# MBus-WeMOS.net
KiCad netlist of a schematic drawn in EAGLE
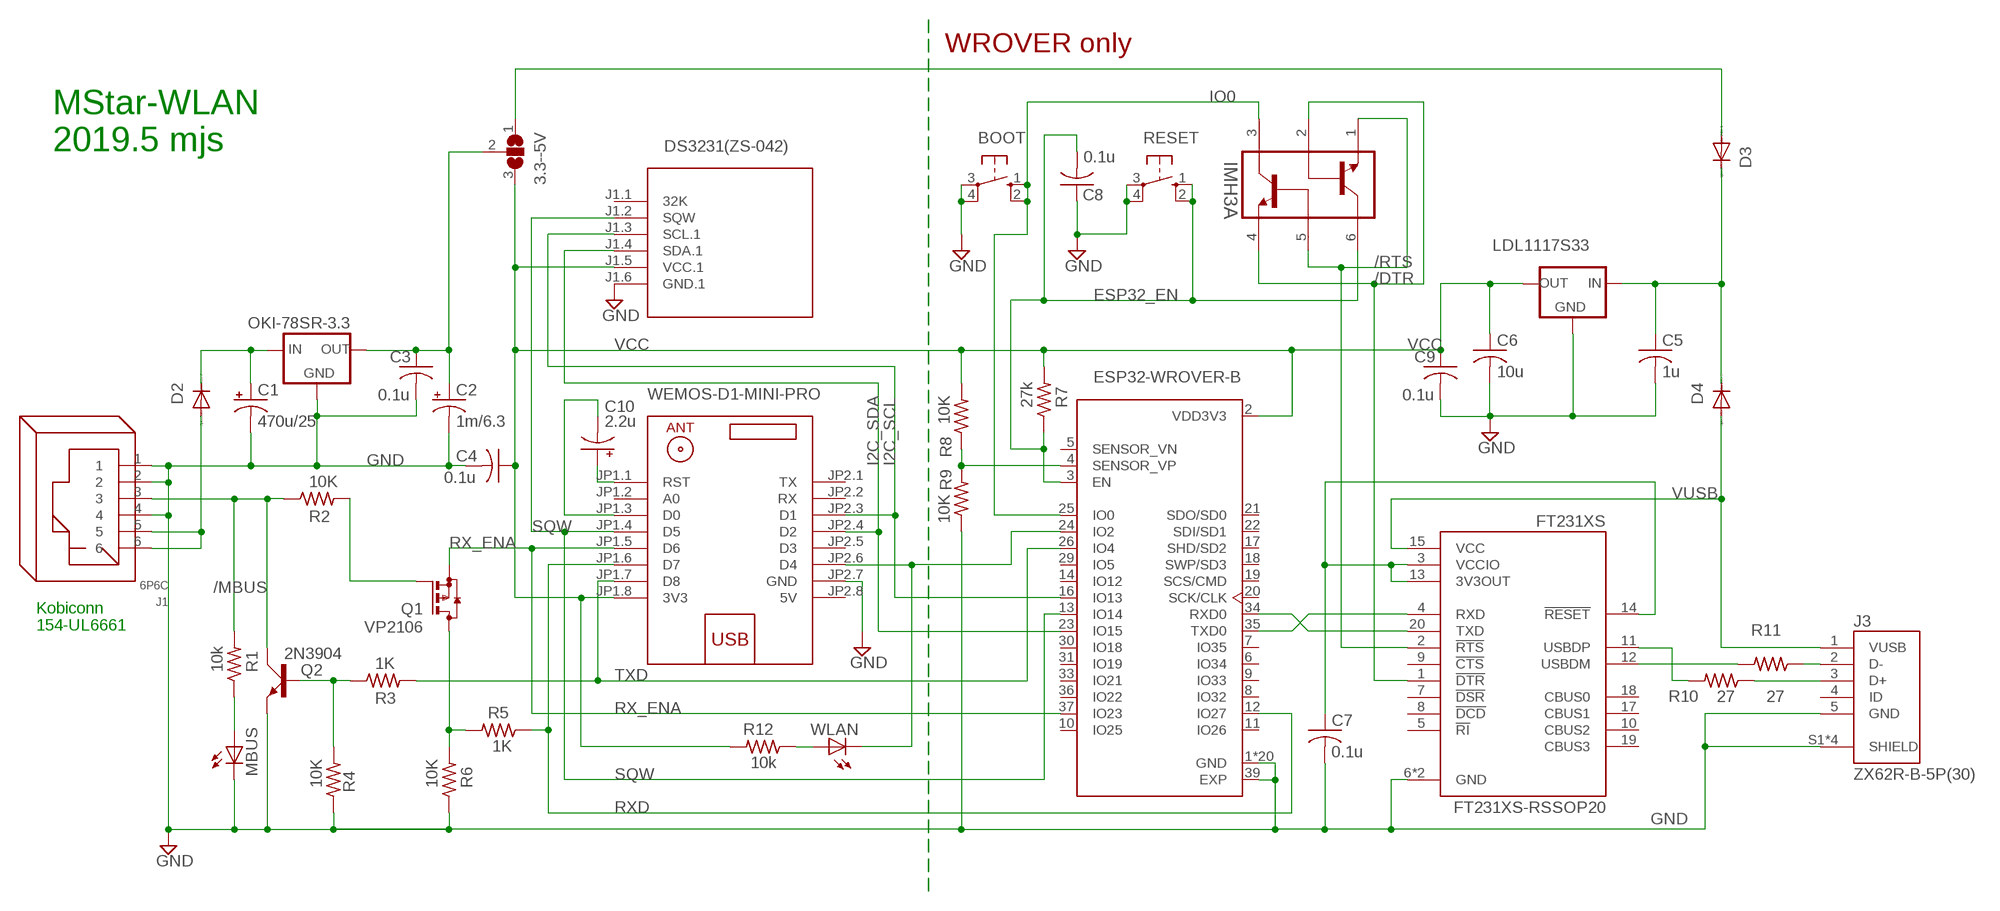
[diagram p0: schematic, sheet 1]

(export (version "E")
  (design (tool "Eeschema 10.0.6"))
  (components
    (comp (ref "3.3--5V")
      (value "SJ2W")
      (footprint "eagle-import:SJ_2")
      (libsource (lib "eagle-import") (part "SJ2W"))
    )
    (comp (ref "BOOT")
      (value "10-XX")
      (footprint "eagle-import:B3F-10XX")
      (fields (field (name "MPN") "B3F-1000"))
      (libsource (lib "eagle-import") (part "10-XX"))
    )
    (comp (ref "C1")
      (value "470u/25")
      (footprint "eagle-import:E3,5-8")
      (libsource (lib "eagle-import") (part "CPOL-USE3.5-8"))
    )
    (comp (ref "C2")
      (value "1m/6.3")
      (footprint "eagle-import:E5-10,5")
      (libsource (lib "eagle-import") (part "CPOL-USE5-10.5"))
    )
    (comp (ref "C3")
      (value "0.1u")
      (footprint "eagle-import:C025-024X044")
      (libsource (lib "eagle-import") (part "C-US025-024X044"))
    )
    (comp (ref "C4")
      (value "0.1u")
      (footprint "eagle-import:C025-024X044")
      (libsource (lib "eagle-import") (part "C-US025-024X044"))
    )
    (comp (ref "C5")
      (value "1u")
      (footprint "eagle-import:C1206")
      (libsource (lib "eagle-import") (part "C-USC1206"))
    )
    (comp (ref "C6")
      (value "10u")
      (footprint "eagle-import:C1206")
      (libsource (lib "eagle-import") (part "C-USC1206"))
    )
    (comp (ref "C7")
      (value "0.1u")
      (footprint "eagle-import:C025-024X044")
      (libsource (lib "eagle-import") (part "C-US025-024X044"))
    )
    (comp (ref "C8")
      (value "0.1u")
      (footprint "eagle-import:C025-024X044")
      (libsource (lib "eagle-import") (part "C-US025-024X044"))
    )
    (comp (ref "C9")
      (value "0.1u")
      (footprint "eagle-import:C025-024X044")
      (libsource (lib "eagle-import") (part "C-US025-024X044"))
    )
    (comp (ref "C10")
      (value "2.2u")
      (footprint "eagle-import:E2,5-5")
      (libsource (lib "eagle-import") (part "CPOL-USE2.5-5"))
    )
    (comp (ref "D2")
      (value "DIODE-D-5")
      (footprint "eagle-import:D-5")
      (libsource (lib "eagle-import") (part "DIODE-D-5"))
    )
    (comp (ref "D3")
      (value "DIODE-D-5")
      (footprint "eagle-import:D-5")
      (libsource (lib "eagle-import") (part "DIODE-D-5"))
    )
    (comp (ref "D4")
      (value "DIODE-D-5")
      (footprint "eagle-import:D-5")
      (libsource (lib "eagle-import") (part "DIODE-D-5"))
    )
    (comp (ref "DS3231(ZS-042)")
      (value "RTC-DS3231-AT24C32-6")
      (footprint "eagle-import:RTC-DS3231-AT24C32-6")
      (libsource (lib "eagle-import") (part "RTC-DS3231-AT24C32-6"))
    )
    (comp (ref "ESP32-WROVER-B")
      (value "ESP32-WROVER-I")
      (footprint "eagle-import:XCVR_ESP32-WROVER-I")
      (fields (field (name "MF") "Espressif Systems"))
      (libsource (lib "eagle-import") (part "ESP32-WROVER-I"))
    )
    (comp (ref "FT231XS")
      (value "FT231XS-RSSOP20")
      (footprint "eagle-import:SSOP20")
      (fields
        (field (name "DIGI-KEY_PART_NUMBER") "768-1129-1-ND")
        (field (name "MF") "FTDI,")
        (field (name "MP") "FT231XS-R")
      )
      (libsource (lib "eagle-import") (part "FT231XS-RSSOP20"))
    )
    (comp (ref "IMH3A")
      (value "IMH3ATSOP6")
      (footprint "eagle-import:TSOP6")
      (libsource (lib "eagle-import") (part "IMH3ATSOP6"))
    )
    (comp (ref "J1")
      (value "6P6C")
      (footprint "eagle-import:RJ12")
      (libsource (lib "eagle-import") (part "RJ12"))
    )
    (comp (ref "J3")
      (value "ZX62R-B-5P(30)")
      (footprint "eagle-import:HRS_ZX62R-B-5P(30)")
      (fields (field (name "MF") "Hirose") (field (name "MP") "ZX62R-B-5P_30_"))
      (libsource (lib "eagle-import") (part "ZX62R-B-5P(30)"))
    )
    (comp (ref "LDL1117S33")
      (value "LM1117MP-3.3")
      (footprint "eagle-import:SOT223")
      (fields (field (name "MF") "Texas Instruments"))
      (libsource (lib "eagle-import") (part "LM1117?-MP3.3"))
    )
    (comp (ref "MBUS")
      (value "LED3MM")
      (footprint "eagle-import:LED3MM")
      (libsource (lib "eagle-import") (part "LED3MM"))
    )
    (comp (ref "OKI-78SR-3.3")
      (value "78MXXS")
      (footprint "eagle-import:78MXXS")
      (libsource (lib "eagle-import") (part "78MXXS"))
    )
    (comp (ref "Q1")
      (value "VP2106")
      (footprint "eagle-import:TO92")
      (libsource (lib "eagle-import") (part "VP2106"))
    )
    (comp (ref "Q2")
      (value "2N3904")
      (footprint "eagle-import:TO92D")
      (libsource (lib "eagle-import") (part "2N3904"))
    )
    (comp (ref "R1")
      (value "10k")
      (footprint "eagle-import:0207_2V")
      (libsource (lib "eagle-import") (part "R-US_0207/2V"))
    )
    (comp (ref "R2")
      (value "10K")
      (footprint "eagle-import:0207_2V")
      (libsource (lib "eagle-import") (part "R-US_0207/2V"))
    )
    (comp (ref "R3")
      (value "1K")
      (footprint "eagle-import:0207_2V")
      (libsource (lib "eagle-import") (part "R-US_0207/2V"))
    )
    (comp (ref "R4")
      (value "10K")
      (footprint "eagle-import:0207_2V")
      (libsource (lib "eagle-import") (part "R-US_0207/2V"))
    )
    (comp (ref "R5")
      (value "1K")
      (footprint "eagle-import:0207_2V")
      (libsource (lib "eagle-import") (part "R-US_0207/2V"))
    )
    (comp (ref "R6")
      (value "10K")
      (footprint "eagle-import:0207_2V")
      (libsource (lib "eagle-import") (part "R-US_0207/2V"))
    )
    (comp (ref "R7")
      (value "27k")
      (footprint "eagle-import:0207_2V")
      (libsource (lib "eagle-import") (part "R-US_0207/2V"))
    )
    (comp (ref "R8")
      (value "10K")
      (footprint "eagle-import:0207_2V")
      (libsource (lib "eagle-import") (part "R-US_0207/2V"))
    )
    (comp (ref "R9")
      (value "10K")
      (footprint "eagle-import:0207_2V")
      (libsource (lib "eagle-import") (part "R-US_0207/2V"))
    )
    (comp (ref "R10")
      (value "27")
      (footprint "eagle-import:0207_2V")
      (libsource (lib "eagle-import") (part "R-US_0207/2V"))
    )
    (comp (ref "R11")
      (value "27")
      (footprint "eagle-import:0207_2V")
      (libsource (lib "eagle-import") (part "R-US_0207/2V"))
    )
    (comp (ref "R12")
      (value "10k")
      (footprint "eagle-import:0207_2V")
      (libsource (lib "eagle-import") (part "R-US_0207/2V"))
    )
    (comp (ref "RESET")
      (value "10-XX")
      (footprint "eagle-import:B3F-10XX")
      (fields (field (name "MPN") "B3F-1000"))
      (libsource (lib "eagle-import") (part "10-XX"))
    )
    (comp (ref "U$1")
      (value "WEMOS-D1-MINI-PRO")
      (footprint "eagle-import:WEMOS-D1-MINI-PRO")
      (libsource (lib "eagle-import") (part "WEMOS-D1-MINI-PRO"))
    )
    (comp (ref "WLAN")
      (value "LED3MM")
      (footprint "eagle-import:LED3MM")
      (libsource (lib "eagle-import") (part "LED3MM"))
    )
  )
  (nets
    (net (code "1") (name "/5V") (class "Default")
      (node (ref "U$1") (pin "JP2.8") (pinfunction "5V_JP2.8") (pintype "power_in"))
    )
    (net (code "2") (name "/ESP32_EN") (class "Default")
      (node (ref "C8") (pin "2") (pinfunction "2_2") (pintype "passive"))
      (node (ref "ESP32-WROVER-B") (pin "3") (pinfunction "EN_3") (pintype "input"))
      (node (ref "IMH3A") (pin "6") (pinfunction "Q1C_6") (pintype "bidirectional"))
      (node (ref "R7") (pin "1") (pinfunction "1_1") (pintype "passive"))
      (node (ref "RESET") (pin "1") (pinfunction "S_1") (pintype "passive"))
      (node (ref "RESET") (pin "2") (pinfunction "S1_2") (pintype "passive"))
    )
    (net (code "3") (name "/I2C_SCL") (class "Default")
      (node (ref "DS3231(ZS-042)") (pin "J1.3") (pinfunction "SCL.1_J1.3") (pintype "bidirectional"))
      (node (ref "ESP32-WROVER-B") (pin "16") (pinfunction "IO13_16") (pintype "bidirectional"))
      (node (ref "U$1") (pin "JP2.3") (pinfunction "D1_JP2.3") (pintype "bidirectional"))
    )
    (net (code "4") (name "/I2C_SDA") (class "Default")
      (node (ref "DS3231(ZS-042)") (pin "J1.4") (pinfunction "SDA.1_J1.4") (pintype "bidirectional"))
      (node (ref "ESP32-WROVER-B") (pin "23") (pinfunction "IO15_23") (pintype "bidirectional"))
      (node (ref "U$1") (pin "JP2.4") (pinfunction "D2_JP2.4") (pintype "bidirectional"))
    )
    (net (code "5") (name "/IO0") (class "Default")
      (node (ref "BOOT") (pin "1") (pinfunction "S_1") (pintype "passive"))
      (node (ref "BOOT") (pin "2") (pinfunction "S1_2") (pintype "passive"))
      (node (ref "ESP32-WROVER-B") (pin "25") (pinfunction "IO0_25") (pintype "bidirectional"))
      (node (ref "IMH3A") (pin "3") (pinfunction "Q2C_3") (pintype "bidirectional"))
    )
    (net (code "6") (name "/RXD") (class "Default")
      (node (ref "ESP32-WROVER-B") (pin "12") (pinfunction "IO27_12") (pintype "bidirectional"))
      (node (ref "R5") (pin "1") (pinfunction "1_1") (pintype "passive"))
      (node (ref "U$1") (pin "JP1.6") (pinfunction "D7_JP1.6") (pintype "bidirectional"))
    )
    (net (code "7") (name "/RX_ENA") (class "Default")
      (node (ref "ESP32-WROVER-B") (pin "37") (pinfunction "IO23_37") (pintype "bidirectional"))
      (node (ref "Q1") (pin "S") (pinfunction "S_S") (pintype "passive"))
      (node (ref "U$1") (pin "JP1.5") (pinfunction "D6_JP1.5") (pintype "bidirectional"))
    )
    (net (code "8") (name "/SQW") (class "Default")
      (node (ref "DS3231(ZS-042)") (pin "J1.2") (pinfunction "SQW_J1.2") (pintype "bidirectional"))
      (node (ref "ESP32-WROVER-B") (pin "13") (pinfunction "IO14_13") (pintype "bidirectional"))
      (node (ref "U$1") (pin "JP1.4") (pinfunction "D5_JP1.4") (pintype "bidirectional"))
    )
    (net (code "9") (name "/TXD") (class "Default")
      (node (ref "ESP32-WROVER-B") (pin "26") (pinfunction "IO4_26") (pintype "bidirectional"))
      (node (ref "R3") (pin "2") (pinfunction "2_2") (pintype "passive"))
      (node (ref "U$1") (pin "JP1.7") (pinfunction "D8_JP1.7") (pintype "bidirectional"))
    )
    (net (code "10") (name "/VCC") (class "Default")
      (node (ref "3.3--5V") (pin "3") (pinfunction "3_3") (pintype "passive"))
      (node (ref "C4") (pin "1") (pinfunction "1_1") (pintype "passive"))
      (node (ref "C6") (pin "1") (pinfunction "1_1") (pintype "passive"))
      (node (ref "C9") (pin "1") (pinfunction "1_1") (pintype "passive"))
      (node (ref "DS3231(ZS-042)") (pin "J1.5") (pinfunction "VCC.1_J1.5") (pintype "power_in"))
      (node (ref "ESP32-WROVER-B") (pin "2") (pinfunction "VDD3V3_2") (pintype "power_in"))
      (node (ref "LDL1117S33") (pin "2") (pinfunction "OUT_2") (pintype "passive"))
      (node (ref "LDL1117S33") (pin "4") (pinfunction "OUT_4") (pintype "passive"))
      (node (ref "R12") (pin "2") (pinfunction "2_2") (pintype "passive"))
      (node (ref "R7") (pin "2") (pinfunction "2_2") (pintype "passive"))
      (node (ref "R8") (pin "2") (pinfunction "2_2") (pintype "passive"))
      (node (ref "U$1") (pin "JP1.8") (pinfunction "3V3_JP1.8") (pintype "power_in"))
    )
    (net (code "11") (name "/VUSB") (class "Default")
      (node (ref "D4") (pin "A") (pinfunction "A_A") (pintype "passive"))
      (node (ref "FT231XS") (pin "15") (pinfunction "VCC_15") (pintype "power_in"))
      (node (ref "J3") (pin "1") (pinfunction "VUSB_1") (pintype "passive"))
    )
    (net (code "12") (name "/{slash}DTR") (class "Default")
      (node (ref "FT231XS") (pin "1") (pinfunction "~{DTR}_1") (pintype "output"))
      (node (ref "IMH3A") (pin "2") (pinfunction "Q1B_2") (pintype "bidirectional"))
      (node (ref "IMH3A") (pin "4") (pinfunction "Q2E_4") (pintype "bidirectional"))
    )
    (net (code "13") (name "/{slash}MBUS") (class "Default")
      (node (ref "J1") (pin "3") (pinfunction "3_3") (pintype "bidirectional"))
      (node (ref "Q2") (pin "C") (pinfunction "C_C") (pintype "passive"))
      (node (ref "R1") (pin "2") (pinfunction "2_2") (pintype "passive"))
      (node (ref "R2") (pin "1") (pinfunction "1_1") (pintype "passive"))
    )
    (net (code "14") (name "/{slash}RTS") (class "Default")
      (node (ref "FT231XS") (pin "2") (pinfunction "~{RTS}_2") (pintype "output"))
      (node (ref "IMH3A") (pin "1") (pinfunction "Q1E_1") (pintype "bidirectional"))
      (node (ref "IMH3A") (pin "5") (pinfunction "Q2B_5") (pintype "bidirectional"))
    )
    (net (code "15") (name "GND") (class "Default")
      (node (ref "BOOT") (pin "3") (pinfunction "P_3") (pintype "passive"))
      (node (ref "BOOT") (pin "4") (pinfunction "P1_4") (pintype "passive"))
      (node (ref "C1") (pin "-") (pinfunction "-_-") (pintype "passive"))
      (node (ref "C2") (pin "-") (pinfunction "-_-") (pintype "passive"))
      (node (ref "C3") (pin "2") (pinfunction "2_2") (pintype "passive"))
      (node (ref "C4") (pin "2") (pinfunction "2_2") (pintype "passive"))
      (node (ref "C5") (pin "2") (pinfunction "2_2") (pintype "passive"))
      (node (ref "C6") (pin "2") (pinfunction "2_2") (pintype "passive"))
      (node (ref "C7") (pin "2") (pinfunction "2_2") (pintype "passive"))
      (node (ref "C8") (pin "1") (pinfunction "1_1") (pintype "passive"))
      (node (ref "C9") (pin "2") (pinfunction "2_2") (pintype "passive"))
      (node (ref "DS3231(ZS-042)") (pin "J1.6") (pinfunction "GND.1_J1.6") (pintype "power_in"))
      (node (ref "ESP32-WROVER-B") (pin "1") (pinfunction "GND_1") (pintype "power_in"))
      (node (ref "ESP32-WROVER-B") (pin "15") (pinfunction "GND_15") (pintype "power_in"))
      (node (ref "ESP32-WROVER-B") (pin "38") (pinfunction "GND_38") (pintype "power_in"))
      (node (ref "ESP32-WROVER-B") (pin "39") (pinfunction "EXP_39") (pintype "power_in"))
      (node (ref "ESP32-WROVER-B") (pin "40") (pinfunction "GND_40") (pintype "power_in"))
      (node (ref "ESP32-WROVER-B") (pin "P$1") (pinfunction "GND_P$1") (pintype "power_in"))
      (node (ref "ESP32-WROVER-B") (pin "P$10") (pinfunction "GND_P$10") (pintype "power_in"))
      (node (ref "ESP32-WROVER-B") (pin "P$11") (pinfunction "GND_P$11") (pintype "power_in"))
      (node (ref "ESP32-WROVER-B") (pin "P$12") (pinfunction "GND_P$12") (pintype "power_in"))
      (node (ref "ESP32-WROVER-B") (pin "P$13") (pinfunction "GND_P$13") (pintype "power_in"))
      (node (ref "ESP32-WROVER-B") (pin "P$14") (pinfunction "GND_P$14") (pintype "power_in"))
      (node (ref "ESP32-WROVER-B") (pin "P$15") (pinfunction "GND_P$15") (pintype "power_in"))
      (node (ref "ESP32-WROVER-B") (pin "P$16") (pinfunction "GND_P$16") (pintype "power_in"))
      (node (ref "ESP32-WROVER-B") (pin "P$2") (pinfunction "GND_P$2") (pintype "power_in"))
      (node (ref "ESP32-WROVER-B") (pin "P$3") (pinfunction "GND_P$3") (pintype "power_in"))
      (node (ref "ESP32-WROVER-B") (pin "P$4") (pinfunction "GND_P$4") (pintype "power_in"))
      (node (ref "ESP32-WROVER-B") (pin "P$5") (pinfunction "GND_P$5") (pintype "power_in"))
      (node (ref "ESP32-WROVER-B") (pin "P$6") (pinfunction "GND_P$6") (pintype "power_in"))
      (node (ref "ESP32-WROVER-B") (pin "P$7") (pinfunction "GND_P$7") (pintype "power_in"))
      (node (ref "ESP32-WROVER-B") (pin "P$8") (pinfunction "GND_P$8") (pintype "power_in"))
      (node (ref "ESP32-WROVER-B") (pin "P$9") (pinfunction "GND_P$9") (pintype "power_in"))
      (node (ref "FT231XS") (pin "16") (pinfunction "GND_16") (pintype "power_in"))
      (node (ref "FT231XS") (pin "6") (pinfunction "GND_6") (pintype "power_in"))
      (node (ref "J1") (pin "1") (pinfunction "1_1") (pintype "bidirectional"))
      (node (ref "J1") (pin "2") (pinfunction "2_2") (pintype "bidirectional"))
      (node (ref "J1") (pin "4") (pinfunction "4_4") (pintype "bidirectional"))
      (node (ref "J3") (pin "5") (pinfunction "GND_5") (pintype "passive"))
      (node (ref "J3") (pin "S1") (pinfunction "SHIELD_S1") (pintype "passive"))
      (node (ref "J3") (pin "S2") (pinfunction "SHIELD_S2") (pintype "passive"))
      (node (ref "J3") (pin "S3") (pinfunction "SHIELD_S3") (pintype "passive"))
      (node (ref "J3") (pin "S6") (pinfunction "SHIELD_S6") (pintype "passive"))
      (node (ref "LDL1117S33") (pin "1") (pinfunction "GND_1") (pintype "input"))
      (node (ref "MBUS") (pin "K") (pinfunction "C_K") (pintype "passive"))
      (node (ref "OKI-78SR-3.3") (pin "GND") (pinfunction "GND_GND") (pintype "input"))
      (node (ref "Q2") (pin "E") (pinfunction "E_E") (pintype "passive"))
      (node (ref "R4") (pin "1") (pinfunction "1_1") (pintype "passive"))
      (node (ref "R6") (pin "1") (pinfunction "1_1") (pintype "passive"))
      (node (ref "R9") (pin "1") (pinfunction "1_1") (pintype "passive"))
      (node (ref "RESET") (pin "3") (pinfunction "P_3") (pintype "passive"))
      (node (ref "RESET") (pin "4") (pinfunction "P1_4") (pintype "passive"))
      (node (ref "U$1") (pin "JP2.7") (pinfunction "GND_JP2.7") (pintype "power_in"))
    )
    (net (code "16") (name "Net-(3.3--5V-Pad1)") (class "Default")
      (node (ref "3.3--5V") (pin "1") (pinfunction "1_1") (pintype "passive"))
      (node (ref "D3") (pin "A") (pinfunction "A_A") (pintype "passive"))
    )
    (net (code "17") (name "Net-(3.3--5V-Pad2)") (class "Default")
      (node (ref "3.3--5V") (pin "2") (pinfunction "2_2") (pintype "passive"))
      (node (ref "C2") (pin "+") (pinfunction "+_+") (pintype "passive"))
      (node (ref "C3") (pin "1") (pinfunction "1_1") (pintype "passive"))
      (node (ref "OKI-78SR-3.3") (pin "OUT") (pinfunction "OUT_OUT") (pintype "passive"))
    )
    (net (code "18") (name "Net-(C1-Pad+)") (class "Default")
      (node (ref "C1") (pin "+") (pinfunction "+_+") (pintype "passive"))
      (node (ref "D2") (pin "C") (pinfunction "C_C") (pintype "passive"))
      (node (ref "OKI-78SR-3.3") (pin "IN") (pinfunction "IN_IN") (pintype "input"))
    )
    (net (code "19") (name "Net-(D2-PadA)") (class "Default")
      (node (ref "D2") (pin "A") (pinfunction "A_A") (pintype "passive"))
      (node (ref "J1") (pin "5") (pinfunction "5_5") (pintype "bidirectional"))
      (node (ref "J1") (pin "6") (pinfunction "6_6") (pintype "bidirectional"))
    )
    (net (code "20") (name "Net-(ESP32-WROVER-B-IO2)") (class "Default")
      (node (ref "ESP32-WROVER-B") (pin "24") (pinfunction "IO2_24") (pintype "bidirectional"))
      (node (ref "U$1") (pin "JP2.6") (pinfunction "D4_JP2.6") (pintype "bidirectional"))
      (node (ref "WLAN") (pin "K") (pinfunction "C_K") (pintype "passive"))
    )
    (net (code "21") (name "Net-(ESP32-WROVER-B-RXD0)") (class "Default")
      (node (ref "ESP32-WROVER-B") (pin "34") (pinfunction "RXD0_34") (pintype "bidirectional"))
      (node (ref "FT231XS") (pin "20") (pinfunction "TXD_20") (pintype "output"))
    )
    (net (code "22") (name "Net-(ESP32-WROVER-B-SENSOR_VP)") (class "Default")
      (node (ref "ESP32-WROVER-B") (pin "4") (pinfunction "SENSOR_VP_4") (pintype "input"))
      (node (ref "R8") (pin "1") (pinfunction "1_1") (pintype "passive"))
      (node (ref "R9") (pin "2") (pinfunction "2_2") (pintype "passive"))
    )
    (net (code "23") (name "Net-(ESP32-WROVER-B-TXD0)") (class "Default")
      (node (ref "ESP32-WROVER-B") (pin "35") (pinfunction "TXD0_35") (pintype "bidirectional"))
      (node (ref "FT231XS") (pin "4") (pinfunction "RXD_4") (pintype "input"))
    )
    (net (code "24") (name "Net-(FT231XS-3V3OUT)") (class "Default")
      (node (ref "C7") (pin "1") (pinfunction "1_1") (pintype "passive"))
      (node (ref "FT231XS") (pin "13") (pinfunction "3V3OUT_13") (pintype "power_in"))
      (node (ref "FT231XS") (pin "14") (pinfunction "~{RESET}_14") (pintype "input"))
      (node (ref "FT231XS") (pin "3") (pinfunction "VCCIO_3") (pintype "power_in"))
    )
    (net (code "25") (name "Net-(FT231XS-USBDM)") (class "Default")
      (node (ref "FT231XS") (pin "12") (pinfunction "USBDM_12") (pintype "input"))
      (node (ref "R11") (pin "2") (pinfunction "2_2") (pintype "passive"))
    )
    (net (code "26") (name "Net-(FT231XS-USBDP)") (class "Default")
      (node (ref "FT231XS") (pin "11") (pinfunction "USBDP_11") (pintype "input"))
      (node (ref "R10") (pin "2") (pinfunction "2_2") (pintype "passive"))
    )
    (net (code "27") (name "Net-(J3-D+)") (class "Default")
      (node (ref "J3") (pin "3") (pinfunction "D+_3") (pintype "passive"))
      (node (ref "R10") (pin "1") (pinfunction "1_1") (pintype "passive"))
    )
    (net (code "28") (name "Net-(J3-D-)") (class "Default")
      (node (ref "J3") (pin "2") (pinfunction "D-_2") (pintype "passive"))
      (node (ref "R11") (pin "1") (pinfunction "1_1") (pintype "passive"))
    )
    (net (code "29") (name "Net-(LDL1117S33-IN)") (class "Default")
      (node (ref "C5") (pin "1") (pinfunction "1_1") (pintype "passive"))
      (node (ref "D3") (pin "C") (pinfunction "C_C") (pintype "passive"))
      (node (ref "D4") (pin "C") (pinfunction "C_C") (pintype "passive"))
      (node (ref "LDL1117S33") (pin "3") (pinfunction "IN_3") (pintype "input"))
    )
    (net (code "30") (name "Net-(MBUS-PadA)") (class "Default")
      (node (ref "MBUS") (pin "A") (pinfunction "A_A") (pintype "passive"))
      (node (ref "R1") (pin "1") (pinfunction "1_1") (pintype "passive"))
    )
    (net (code "31") (name "Net-(Q1-PadD)") (class "Default")
      (node (ref "Q1") (pin "D") (pinfunction "D_D") (pintype "passive"))
      (node (ref "R5") (pin "2") (pinfunction "2_2") (pintype "passive"))
      (node (ref "R6") (pin "2") (pinfunction "2_2") (pintype "passive"))
    )
    (net (code "32") (name "Net-(Q1-PadG)") (class "Default")
      (node (ref "Q1") (pin "G") (pinfunction "G_G") (pintype "passive"))
      (node (ref "R2") (pin "2") (pinfunction "2_2") (pintype "passive"))
    )
    (net (code "33") (name "Net-(Q2-PadB)") (class "Default")
      (node (ref "Q2") (pin "B") (pinfunction "B_B") (pintype "passive"))
      (node (ref "R3") (pin "1") (pinfunction "1_1") (pintype "passive"))
      (node (ref "R4") (pin "2") (pinfunction "2_2") (pintype "passive"))
    )
    (net (code "34") (name "Net-(R12-Pad1)") (class "Default")
      (node (ref "R12") (pin "1") (pinfunction "1_1") (pintype "passive"))
      (node (ref "WLAN") (pin "A") (pinfunction "A_A") (pintype "passive"))
    )
    (net (code "35") (name "Net-(U$1-D0)") (class "Default")
      (node (ref "C10") (pin "-") (pinfunction "-_-") (pintype "passive"))
      (node (ref "U$1") (pin "JP1.3") (pinfunction "D0_JP1.3") (pintype "bidirectional"))
    )
    (net (code "36") (name "Net-(U$1-RST)") (class "Default")
      (node (ref "C10") (pin "+") (pinfunction "+_+") (pintype "passive"))
      (node (ref "U$1") (pin "JP1.1") (pinfunction "RST_JP1.1") (pintype "bidirectional"))
    )
    (net (code "37") (name "unconnected-(DS3231(ZS-042)-32K-PadJ1.1)") (class "Default")
      (node (ref "DS3231(ZS-042)") (pin "J1.1") (pinfunction "32K_J1.1") (pintype "bidirectional"))
    )
    (net (code "38") (name "unconnected-(ESP32-WROVER-B-IO5-Pad29)") (class "Default")
      (node (ref "ESP32-WROVER-B") (pin "29") (pinfunction "IO5_29") (pintype "bidirectional"))
    )
    (net (code "39") (name "unconnected-(ESP32-WROVER-B-IO12-Pad14)") (class "Default")
      (node (ref "ESP32-WROVER-B") (pin "14") (pinfunction "IO12_14") (pintype "bidirectional"))
    )
    (net (code "40") (name "unconnected-(ESP32-WROVER-B-IO18-Pad30)") (class "Default")
      (node (ref "ESP32-WROVER-B") (pin "30") (pinfunction "IO18_30") (pintype "bidirectional"))
    )
    (net (code "41") (name "unconnected-(ESP32-WROVER-B-IO19-Pad31)") (class "Default")
      (node (ref "ESP32-WROVER-B") (pin "31") (pinfunction "IO19_31") (pintype "bidirectional"))
    )
    (net (code "42") (name "unconnected-(ESP32-WROVER-B-IO21-Pad33)") (class "Default")
      (node (ref "ESP32-WROVER-B") (pin "33") (pinfunction "IO21_33") (pintype "bidirectional"))
    )
    (net (code "43") (name "unconnected-(ESP32-WROVER-B-IO22-Pad36)") (class "Default")
      (node (ref "ESP32-WROVER-B") (pin "36") (pinfunction "IO22_36") (pintype "bidirectional"))
    )
    (net (code "44") (name "unconnected-(ESP32-WROVER-B-IO25-Pad10)") (class "Default")
      (node (ref "ESP32-WROVER-B") (pin "10") (pinfunction "IO25_10") (pintype "bidirectional"))
    )
    (net (code "45") (name "unconnected-(ESP32-WROVER-B-IO26-Pad11)") (class "Default")
      (node (ref "ESP32-WROVER-B") (pin "11") (pinfunction "IO26_11") (pintype "bidirectional"))
    )
    (net (code "46") (name "unconnected-(ESP32-WROVER-B-IO32-Pad8)") (class "Default")
      (node (ref "ESP32-WROVER-B") (pin "8") (pinfunction "IO32_8") (pintype "bidirectional"))
    )
    (net (code "47") (name "unconnected-(ESP32-WROVER-B-IO33-Pad9)") (class "Default")
      (node (ref "ESP32-WROVER-B") (pin "9") (pinfunction "IO33_9") (pintype "bidirectional"))
    )
    (net (code "48") (name "unconnected-(ESP32-WROVER-B-IO34-Pad6)") (class "Default")
      (node (ref "ESP32-WROVER-B") (pin "6") (pinfunction "IO34_6") (pintype "input"))
    )
    (net (code "49") (name "unconnected-(ESP32-WROVER-B-IO35-Pad7)") (class "Default")
      (node (ref "ESP32-WROVER-B") (pin "7") (pinfunction "IO35_7") (pintype "input"))
    )
    (net (code "50") (name "unconnected-(ESP32-WROVER-B-SCK{slash}CLK-Pad20)") (class "Default")
      (node (ref "ESP32-WROVER-B") (pin "20") (pinfunction "SCK/CLK_20") (pintype "bidirectional"))
    )
    (net (code "51") (name "unconnected-(ESP32-WROVER-B-SCS{slash}CMD-Pad19)") (class "Default")
      (node (ref "ESP32-WROVER-B") (pin "19") (pinfunction "SCS/CMD_19") (pintype "bidirectional"))
    )
    (net (code "52") (name "unconnected-(ESP32-WROVER-B-SDI{slash}SD1-Pad22)") (class "Default")
      (node (ref "ESP32-WROVER-B") (pin "22") (pinfunction "SDI/SD1_22") (pintype "bidirectional"))
    )
    (net (code "53") (name "unconnected-(ESP32-WROVER-B-SDO{slash}SD0-Pad21)") (class "Default")
      (node (ref "ESP32-WROVER-B") (pin "21") (pinfunction "SDO/SD0_21") (pintype "bidirectional"))
    )
    (net (code "54") (name "unconnected-(ESP32-WROVER-B-SENSOR_VN-Pad5)") (class "Default")
      (node (ref "ESP32-WROVER-B") (pin "5") (pinfunction "SENSOR_VN_5") (pintype "input"))
    )
    (net (code "55") (name "unconnected-(ESP32-WROVER-B-SHD{slash}SD2-Pad17)") (class "Default")
      (node (ref "ESP32-WROVER-B") (pin "17") (pinfunction "SHD/SD2_17") (pintype "bidirectional"))
    )
    (net (code "56") (name "unconnected-(ESP32-WROVER-B-SWP{slash}SD3-Pad18)") (class "Default")
      (node (ref "ESP32-WROVER-B") (pin "18") (pinfunction "SWP/SD3_18") (pintype "bidirectional"))
    )
    (net (code "57") (name "unconnected-(FT231XS-CBUS0-Pad18)") (class "Default")
      (node (ref "FT231XS") (pin "18") (pinfunction "CBUS0_18") (pintype "bidirectional"))
    )
    (net (code "58") (name "unconnected-(FT231XS-CBUS1-Pad17)") (class "Default")
      (node (ref "FT231XS") (pin "17") (pinfunction "CBUS1_17") (pintype "bidirectional"))
    )
    (net (code "59") (name "unconnected-(FT231XS-CBUS2-Pad10)") (class "Default")
      (node (ref "FT231XS") (pin "10") (pinfunction "CBUS2_10") (pintype "bidirectional"))
    )
    (net (code "60") (name "unconnected-(FT231XS-CBUS3-Pad19)") (class "Default")
      (node (ref "FT231XS") (pin "19") (pinfunction "CBUS3_19") (pintype "bidirectional"))
    )
    (net (code "61") (name "unconnected-(FT231XS-~{CTS}-Pad9)") (class "Default")
      (node (ref "FT231XS") (pin "9") (pinfunction "~{CTS}_9") (pintype "input"))
    )
    (net (code "62") (name "unconnected-(FT231XS-~{DCD}-Pad8)") (class "Default")
      (node (ref "FT231XS") (pin "8") (pinfunction "~{DCD}_8") (pintype "input"))
    )
    (net (code "63") (name "unconnected-(FT231XS-~{DSR}-Pad7)") (class "Default")
      (node (ref "FT231XS") (pin "7") (pinfunction "~{DSR}_7") (pintype "input"))
    )
    (net (code "64") (name "unconnected-(FT231XS-~{RI}-Pad5)") (class "Default")
      (node (ref "FT231XS") (pin "5") (pinfunction "~{RI}_5") (pintype "input"))
    )
    (net (code "65") (name "unconnected-(J3-ID-Pad4)") (class "Default")
      (node (ref "J3") (pin "4") (pinfunction "ID_4") (pintype "passive"))
    )
    (net (code "66") (name "unconnected-(U$1-A0-PadJP1.2)") (class "Default")
      (node (ref "U$1") (pin "JP1.2") (pinfunction "A0_JP1.2") (pintype "bidirectional"))
    )
    (net (code "67") (name "unconnected-(U$1-D3-PadJP2.5)") (class "Default")
      (node (ref "U$1") (pin "JP2.5") (pinfunction "D3_JP2.5") (pintype "bidirectional"))
    )
    (net (code "68") (name "unconnected-(U$1-RX-PadJP2.2)") (class "Default")
      (node (ref "U$1") (pin "JP2.2") (pinfunction "RX_JP2.2") (pintype "bidirectional"))
    )
    (net (code "69") (name "unconnected-(U$1-TX-PadJP2.1)") (class "Default")
      (node (ref "U$1") (pin "JP2.1") (pinfunction "TX_JP2.1") (pintype "bidirectional"))
    )
  )
)
